# ch3.net
KiCad netlist of a schematic drawn in EAGLE
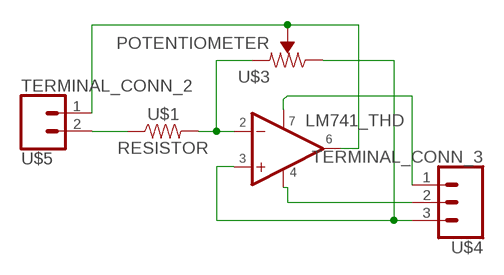
[diagram p0: schematic, sheet 1]

(export (version "E")
  (design (tool "Eeschema 10.0.6"))
  (components
    (comp (ref "U$1")
      (value "RESISTOR")
      (footprint "eagle-import:RESISTOR")
      (libsource (lib "eagle-import") (part "RESISTOR"))
    )
    (comp (ref "U$2")
      (value "IC-LM741")
      (footprint "eagle-import:IC-LM741")
      (libsource (lib "eagle-import") (part "IC-LM741"))
    )
    (comp (ref "U$3")
      (value "POTENTIOMETER")
      (footprint "eagle-import:POTENTIOMETER")
      (libsource (lib "eagle-import") (part "POTENTIOMETER"))
    )
    (comp (ref "U$4")
      (value "TERMINAL_CONN_3")
      (footprint "eagle-import:TERMINAL-CONN_3")
      (libsource (lib "eagle-import") (part "TERMINAL_CONN_3"))
    )
    (comp (ref "U$5")
      (value "TERMINAL_CONN_2")
      (footprint "eagle-import:TERMINAL_CONN_2")
      (libsource (lib "eagle-import") (part "TERMINAL_CONN_2"))
    )
  )
  (nets
    (net (code "1") (name "Net-(U$1-Pad1)") (class "Default")
      (node (ref "U$1") (pin "1") (pinfunction "1_1") (pintype "passive"))
      (node (ref "U$5") (pin "2") (pinfunction "2_2") (pintype "passive"))
    )
    (net (code "2") (name "Net-(U$2-+IN)") (class "Default")
      (node (ref "U$2") (pin "3") (pinfunction "+IN_3") (pintype "input"))
      (node (ref "U$3") (pin "3") (pinfunction "CW_3") (pintype "passive"))
      (node (ref "U$4") (pin "3") (pinfunction "3_3") (pintype "passive"))
    )
    (net (code "3") (name "Net-(U$2--IN)") (class "Default")
      (node (ref "U$1") (pin "2") (pinfunction "2_2") (pintype "passive"))
      (node (ref "U$2") (pin "2") (pinfunction "-IN_2") (pintype "input"))
      (node (ref "U$3") (pin "1") (pinfunction "CCW_1") (pintype "passive"))
    )
    (net (code "4") (name "Net-(U$2-OUT)") (class "Default")
      (node (ref "U$2") (pin "6") (pinfunction "OUT_6") (pintype "output"))
      (node (ref "U$3") (pin "2") (pinfunction "WIPER_2") (pintype "passive"))
      (node (ref "U$5") (pin "1") (pinfunction "1_1") (pintype "passive"))
    )
    (net (code "5") (name "Net-(U$2-Pad4)") (class "Default")
      (node (ref "U$2") (pin "4") (pinfunction "4_4") (pintype "bidirectional"))
      (node (ref "U$4") (pin "2") (pinfunction "2_2") (pintype "passive"))
    )
    (net (code "6") (name "Net-(U$2-Pad7)") (class "Default")
      (node (ref "U$2") (pin "7") (pinfunction "7_7") (pintype "bidirectional"))
      (node (ref "U$4") (pin "1") (pinfunction "1_1") (pintype "passive"))
    )
  )
)
